# RS485_RX.net
KiCad netlist of a schematic drawn in EAGLE
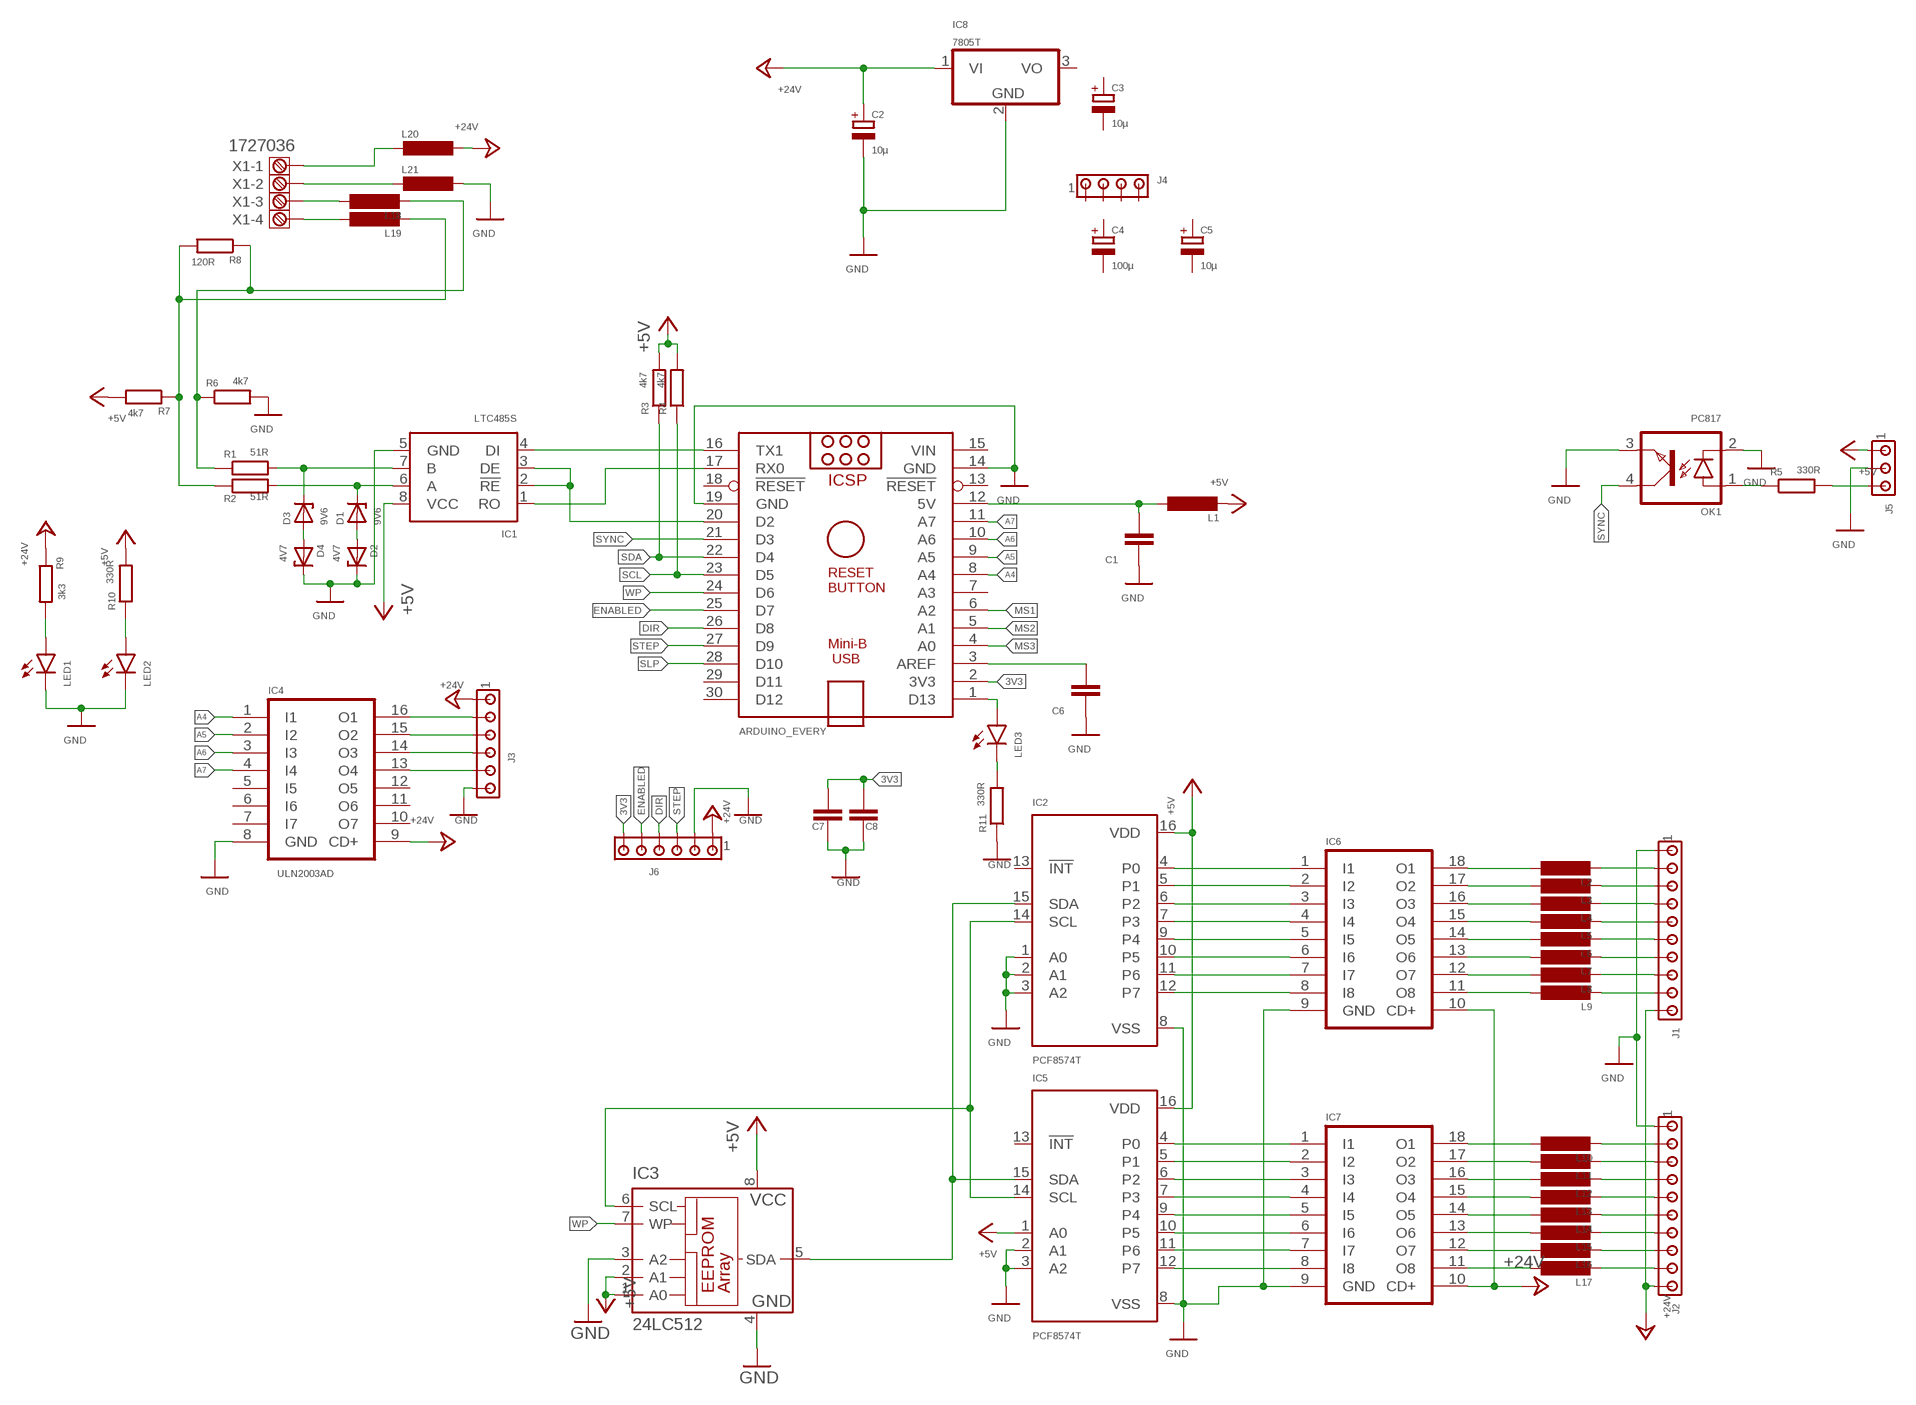
[diagram p0: schematic, sheet 1]

(export (version "E")
  (design (tool "Eeschema 10.0.6"))
  (components
    (comp (ref "ARDUINO_EVERY")
      (value "ARDUINO_NANO")
      (footprint "eagle-import:ARDUINO_NANO")
      (libsource (lib "eagle-import") (part "ARDUINO_NANO"))
    )
    (comp (ref "C1")
      (value "C-EUC0805K")
      (footprint "eagle-import:C0805K")
      (libsource (lib "eagle-import") (part "C-EUC0805K"))
    )
    (comp (ref "C2")
      (value "10µ")
      (footprint "eagle-import:150CLZ-0810")
      (libsource (lib "eagle-import") (part "CPOL-EU150CLZ-0810"))
    )
    (comp (ref "C3")
      (value "10µ")
      (footprint "eagle-import:150CLZ-0810")
      (libsource (lib "eagle-import") (part "CPOL-EU150CLZ-0810"))
    )
    (comp (ref "C4")
      (value "100µ")
      (footprint "eagle-import:150CLZ-0810")
      (libsource (lib "eagle-import") (part "CPOL-EU150CLZ-0810"))
    )
    (comp (ref "C5")
      (value "10µ")
      (footprint "eagle-import:150CLZ-0810")
      (libsource (lib "eagle-import") (part "CPOL-EU150CLZ-0810"))
    )
    (comp (ref "C6")
      (value "C-EUC0805K")
      (footprint "eagle-import:C0805K")
      (libsource (lib "eagle-import") (part "C-EUC0805K"))
    )
    (comp (ref "C7")
      (value "C-EUC0805K")
      (footprint "eagle-import:C0805K")
      (libsource (lib "eagle-import") (part "C-EUC0805K"))
    )
    (comp (ref "C8")
      (value "C-EUC0805K")
      (footprint "eagle-import:C0805K")
      (libsource (lib "eagle-import") (part "C-EUC0805K"))
    )
    (comp (ref "D1")
      (value "9V6")
      (footprint "eagle-import:SOD80C")
      (libsource (lib "eagle-import") (part "ZENER-DIODESOD80C"))
    )
    (comp (ref "D2")
      (value "4V7")
      (footprint "eagle-import:SOD80C")
      (libsource (lib "eagle-import") (part "ZENER-DIODESOD80C"))
    )
    (comp (ref "D3")
      (value "9V6")
      (footprint "eagle-import:SOD80C")
      (libsource (lib "eagle-import") (part "ZENER-DIODESOD80C"))
    )
    (comp (ref "D4")
      (value "4V7")
      (footprint "eagle-import:SOD80C")
      (libsource (lib "eagle-import") (part "ZENER-DIODESOD80C"))
    )
    (comp (ref "IC1")
      (value "LTC485S")
      (footprint "eagle-import:SOIC8")
      (libsource (lib "eagle-import") (part "LTC485S"))
    )
    (comp (ref "IC2")
      (value "PCF8574T")
      (footprint "eagle-import:SO16W")
      (fields (field (name "MPN") "PCF8574T/3,512"))
      (libsource (lib "eagle-import") (part "PCF8574T"))
    )
    (comp (ref "IC3")
      (value "24LC512")
      (footprint "eagle-import:SO-08")
      (fields (field (name "MF") "MICROCHIP") (field (name "MPN") "24LC128-I/SNG"))
      (libsource (lib "eagle-import") (part "24SNLC128"))
    )
    (comp (ref "IC4")
      (value "ULN2003AD")
      (footprint "eagle-import:SO16")
      (libsource (lib "eagle-import") (part "ULN2003AD"))
    )
    (comp (ref "IC5")
      (value "PCF8574T")
      (footprint "eagle-import:SO16W")
      (fields (field (name "MPN") "PCF8574T/3,512"))
      (libsource (lib "eagle-import") (part "PCF8574T"))
    )
    (comp (ref "IC6")
      (value "ULN2803A")
      (footprint "eagle-import:DIL18")
      (libsource (lib "eagle-import") (part "ULN2803A"))
    )
    (comp (ref "IC7")
      (value "ULN2803A")
      (footprint "eagle-import:DIL18")
      (libsource (lib "eagle-import") (part "ULN2803A"))
    )
    (comp (ref "IC8")
      (value "7805T")
      (footprint "eagle-import:TO220H")
      (libsource (lib "eagle-import") (part "78T05"))
    )
    (comp (ref "J1")
      (value "MTA10-100")
      (footprint "eagle-import:10X10MTA")
      (libsource (lib "eagle-import") (part "MTA10-100"))
    )
    (comp (ref "J2")
      (value "MTA10-100")
      (footprint "eagle-import:10X10MTA")
      (libsource (lib "eagle-import") (part "MTA10-100"))
    )
    (comp (ref "J3")
      (value "MTA06-100")
      (footprint "eagle-import:10X06MTA")
      (libsource (lib "eagle-import") (part "MTA06-100"))
    )
    (comp (ref "J4")
      (value "MTA04-156")
      (footprint "eagle-import:1X4MTA")
      (libsource (lib "eagle-import") (part "MTA04-156"))
    )
    (comp (ref "J5")
      (value "MTA03-100")
      (footprint "eagle-import:10X03MTA")
      (libsource (lib "eagle-import") (part "MTA03-100"))
    )
    (comp (ref "J6")
      (value "MTA06-100")
      (footprint "eagle-import:10X06MTA")
      (libsource (lib "eagle-import") (part "MTA06-100"))
    )
    (comp (ref "L1")
      (value "L-EUL1812")
      (footprint "eagle-import:L1812")
      (libsource (lib "eagle-import") (part "L-EUL1812"))
    )
    (comp (ref "L2")
      (value "L-EUL1812")
      (footprint "eagle-import:L1812")
      (libsource (lib "eagle-import") (part "L-EUL1812"))
    )
    (comp (ref "L3")
      (value "L-EUL1812")
      (footprint "eagle-import:L1812")
      (libsource (lib "eagle-import") (part "L-EUL1812"))
    )
    (comp (ref "L4")
      (value "L-EUL1812")
      (footprint "eagle-import:L1812")
      (libsource (lib "eagle-import") (part "L-EUL1812"))
    )
    (comp (ref "L5")
      (value "L-EUL1812")
      (footprint "eagle-import:L1812")
      (libsource (lib "eagle-import") (part "L-EUL1812"))
    )
    (comp (ref "L6")
      (value "L-EUL1812")
      (footprint "eagle-import:L1812")
      (libsource (lib "eagle-import") (part "L-EUL1812"))
    )
    (comp (ref "L7")
      (value "L-EUL1812")
      (footprint "eagle-import:L1812")
      (libsource (lib "eagle-import") (part "L-EUL1812"))
    )
    (comp (ref "L8")
      (value "L-EUL1812")
      (footprint "eagle-import:L1812")
      (libsource (lib "eagle-import") (part "L-EUL1812"))
    )
    (comp (ref "L9")
      (value "L-EUL1812")
      (footprint "eagle-import:L1812")
      (libsource (lib "eagle-import") (part "L-EUL1812"))
    )
    (comp (ref "L10")
      (value "L-EUL1812")
      (footprint "eagle-import:L1812")
      (libsource (lib "eagle-import") (part "L-EUL1812"))
    )
    (comp (ref "L11")
      (value "L-EUL1812")
      (footprint "eagle-import:L1812")
      (libsource (lib "eagle-import") (part "L-EUL1812"))
    )
    (comp (ref "L12")
      (value "L-EUL1812")
      (footprint "eagle-import:L1812")
      (libsource (lib "eagle-import") (part "L-EUL1812"))
    )
    (comp (ref "L13")
      (value "L-EUL1812")
      (footprint "eagle-import:L1812")
      (libsource (lib "eagle-import") (part "L-EUL1812"))
    )
    (comp (ref "L14")
      (value "L-EUL1812")
      (footprint "eagle-import:L1812")
      (libsource (lib "eagle-import") (part "L-EUL1812"))
    )
    (comp (ref "L15")
      (value "L-EUL1812")
      (footprint "eagle-import:L1812")
      (libsource (lib "eagle-import") (part "L-EUL1812"))
    )
    (comp (ref "L16")
      (value "L-EUL1812")
      (footprint "eagle-import:L1812")
      (libsource (lib "eagle-import") (part "L-EUL1812"))
    )
    (comp (ref "L17")
      (value "L-EUL1812")
      (footprint "eagle-import:L1812")
      (libsource (lib "eagle-import") (part "L-EUL1812"))
    )
    (comp (ref "L18")
      (value "L-EUL1812")
      (footprint "eagle-import:L1812")
      (libsource (lib "eagle-import") (part "L-EUL1812"))
    )
    (comp (ref "L19")
      (value "L-EUL1812")
      (footprint "eagle-import:L1812")
      (libsource (lib "eagle-import") (part "L-EUL1812"))
    )
    (comp (ref "L20")
      (value "DO3316P")
      (footprint "eagle-import:DO3316P")
      (libsource (lib "eagle-import") (part "DO3316P"))
    )
    (comp (ref "L21")
      (value "DO3316P")
      (footprint "eagle-import:DO3316P")
      (libsource (lib "eagle-import") (part "DO3316P"))
    )
    (comp (ref "LED1")
      (value "LEDCHIPLED_1206")
      (footprint "eagle-import:CHIPLED_1206")
      (libsource (lib "eagle-import") (part "LEDCHIPLED_1206"))
    )
    (comp (ref "LED2")
      (value "LEDCHIPLED_1206")
      (footprint "eagle-import:CHIPLED_1206")
      (libsource (lib "eagle-import") (part "LEDCHIPLED_1206"))
    )
    (comp (ref "LED3")
      (value "LEDCHIPLED_1206")
      (footprint "eagle-import:CHIPLED_1206")
      (libsource (lib "eagle-import") (part "LEDCHIPLED_1206"))
    )
    (comp (ref "OK1")
      (value "PC817")
      (footprint "eagle-import:DIL04")
      (fields (field (name "MPN") "PC817X4J000F"))
      (libsource (lib "eagle-import") (part "PC817"))
    )
    (comp (ref "R1")
      (value "51R")
      (footprint "eagle-import:R0805")
      (libsource (lib "eagle-import") (part "R-EU_R0805"))
    )
    (comp (ref "R2")
      (value "51R")
      (footprint "eagle-import:R0805")
      (libsource (lib "eagle-import") (part "R-EU_R0805"))
    )
    (comp (ref "R3")
      (value "4k7")
      (footprint "eagle-import:R0805")
      (libsource (lib "eagle-import") (part "R-EU_R0805"))
    )
    (comp (ref "R4")
      (value "4k7")
      (footprint "eagle-import:R0805")
      (libsource (lib "eagle-import") (part "R-EU_R0805"))
    )
    (comp (ref "R5")
      (value "330R")
      (footprint "eagle-import:R0805")
      (libsource (lib "eagle-import") (part "R-EU_R0805"))
    )
    (comp (ref "R6")
      (value "4k7")
      (footprint "eagle-import:R0805")
      (libsource (lib "eagle-import") (part "R-EU_R0805"))
    )
    (comp (ref "R7")
      (value "4k7")
      (footprint "eagle-import:R0805")
      (libsource (lib "eagle-import") (part "R-EU_R0805"))
    )
    (comp (ref "R8")
      (value "120R")
      (footprint "eagle-import:R0805")
      (libsource (lib "eagle-import") (part "R-EU_R0805"))
    )
    (comp (ref "R9")
      (value "3k3")
      (footprint "eagle-import:R0805")
      (libsource (lib "eagle-import") (part "R-EU_R0805"))
    )
    (comp (ref "R10")
      (value "330R")
      (footprint "eagle-import:R0805")
      (libsource (lib "eagle-import") (part "R-EU_R0805"))
    )
    (comp (ref "R11")
      (value "330R")
      (footprint "eagle-import:R0805")
      (libsource (lib "eagle-import") (part "R-EU_R0805"))
    )
    (comp (ref "X1")
      (value "1727036")
      (footprint "eagle-import:1727036")
      (fields (field (name "MF") "FARNELL"))
      (libsource (lib "eagle-import") (part "1727036"))
    )
  )
  (nets
    (net (code "1") (name "+5V") (class "Default")
      (node (ref "IC1") (pin "8") (pinfunction "VCC_8") (pintype "input"))
      (node (ref "IC2") (pin "16") (pinfunction "VDD_16") (pintype "power_in"))
      (node (ref "IC3") (pin "1") (pinfunction "A0_1") (pintype "input"))
      (node (ref "IC3") (pin "2") (pinfunction "A1_2") (pintype "input"))
      (node (ref "IC3") (pin "8") (pinfunction "VCC_8") (pintype "power_in"))
      (node (ref "IC5") (pin "1") (pinfunction "A0_1") (pintype "input"))
      (node (ref "IC5") (pin "16") (pinfunction "VDD_16") (pintype "power_in"))
      (node (ref "J5") (pin "1") (pinfunction "1_1") (pintype "passive"))
      (node (ref "L1") (pin "2") (pinfunction "2_2") (pintype "passive"))
      (node (ref "R10") (pin "2") (pinfunction "2_2") (pintype "passive"))
      (node (ref "R3") (pin "2") (pinfunction "2_2") (pintype "passive"))
      (node (ref "R4") (pin "2") (pinfunction "2_2") (pintype "passive"))
      (node (ref "R7") (pin "2") (pinfunction "2_2") (pintype "passive"))
    )
    (net (code "2") (name "+24V") (class "Default")
      (node (ref "C2") (pin "+") (pinfunction "+_+") (pintype "passive"))
      (node (ref "IC4") (pin "9") (pinfunction "CD+_9") (pintype "passive"))
      (node (ref "IC6") (pin "10") (pinfunction "CD+_10") (pintype "passive"))
      (node (ref "IC7") (pin "10") (pinfunction "CD+_10") (pintype "passive"))
      (node (ref "IC8") (pin "1") (pinfunction "VI_1") (pintype "input"))
      (node (ref "J1") (pin "10") (pinfunction "10_10") (pintype "passive"))
      (node (ref "J2") (pin "10") (pinfunction "10_10") (pintype "passive"))
      (node (ref "J3") (pin "1") (pinfunction "1_1") (pintype "passive"))
      (node (ref "J6") (pin "1") (pinfunction "1_1") (pintype "passive"))
      (node (ref "L20") (pin "2") (pinfunction "2_2") (pintype "passive"))
      (node (ref "R9") (pin "1") (pinfunction "1_1") (pintype "passive"))
    )
    (net (code "3") (name "/VIN") (class "Default")
      (node (ref "ARDUINO_EVERY") (pin "15") (pinfunction "VIN_15") (pintype "power_in"))
    )
    (net (code "4") (name "3V3") (class "Default")
      (node (ref "ARDUINO_EVERY") (pin "2") (pinfunction "3V3_2") (pintype "output"))
      (node (ref "C7") (pin "1") (pinfunction "1_1") (pintype "passive"))
      (node (ref "C8") (pin "1") (pinfunction "1_1") (pintype "passive"))
      (node (ref "J6") (pin "6") (pinfunction "6_6") (pintype "passive"))
    )
    (net (code "5") (name "A4") (class "Default")
      (node (ref "ARDUINO_EVERY") (pin "8") (pinfunction "A4_8") (pintype "bidirectional"))
      (node (ref "IC4") (pin "1") (pinfunction "I1_1") (pintype "input"))
    )
    (net (code "6") (name "A5") (class "Default")
      (node (ref "ARDUINO_EVERY") (pin "9") (pinfunction "A5_9") (pintype "bidirectional"))
      (node (ref "IC4") (pin "2") (pinfunction "I2_2") (pintype "input"))
    )
    (net (code "7") (name "A6") (class "Default")
      (node (ref "ARDUINO_EVERY") (pin "10") (pinfunction "A6_10") (pintype "bidirectional"))
      (node (ref "IC4") (pin "3") (pinfunction "I3_3") (pintype "input"))
    )
    (net (code "8") (name "A7") (class "Default")
      (node (ref "ARDUINO_EVERY") (pin "11") (pinfunction "A7_11") (pintype "bidirectional"))
      (node (ref "IC4") (pin "4") (pinfunction "I4_4") (pintype "input"))
    )
    (net (code "9") (name "DIR") (class "Default")
      (node (ref "ARDUINO_EVERY") (pin "26") (pinfunction "D8_26") (pintype "bidirectional"))
      (node (ref "J6") (pin "4") (pinfunction "4_4") (pintype "passive"))
    )
    (net (code "10") (name "ENABLED") (class "Default")
      (node (ref "ARDUINO_EVERY") (pin "25") (pinfunction "D7_25") (pintype "bidirectional"))
      (node (ref "J6") (pin "5") (pinfunction "5_5") (pintype "passive"))
    )
    (net (code "11") (name "GND") (class "Default")
      (node (ref "ARDUINO_EVERY") (pin "14") (pinfunction "GND_14") (pintype "power_in"))
      (node (ref "ARDUINO_EVERY") (pin "19") (pinfunction "GND_19") (pintype "power_in"))
      (node (ref "C1") (pin "2") (pinfunction "2_2") (pintype "passive"))
      (node (ref "C2") (pin "-") (pinfunction "-_-") (pintype "passive"))
      (node (ref "C6") (pin "2") (pinfunction "2_2") (pintype "passive"))
      (node (ref "C7") (pin "2") (pinfunction "2_2") (pintype "passive"))
      (node (ref "C8") (pin "2") (pinfunction "2_2") (pintype "passive"))
      (node (ref "D2") (pin "C") (pinfunction "C_C") (pintype "passive"))
      (node (ref "D4") (pin "C") (pinfunction "C_C") (pintype "passive"))
      (node (ref "IC1") (pin "5") (pinfunction "GND_5") (pintype "input"))
      (node (ref "IC2") (pin "1") (pinfunction "A0_1") (pintype "input"))
      (node (ref "IC2") (pin "2") (pinfunction "A1_2") (pintype "input"))
      (node (ref "IC2") (pin "3") (pinfunction "A2_3") (pintype "input"))
      (node (ref "IC2") (pin "8") (pinfunction "VSS_8") (pintype "power_in"))
      (node (ref "IC3") (pin "3") (pinfunction "A2_3") (pintype "input"))
      (node (ref "IC3") (pin "4") (pinfunction "GND_4") (pintype "power_in"))
      (node (ref "IC4") (pin "8") (pinfunction "GND_8") (pintype "power_in"))
      (node (ref "IC5") (pin "2") (pinfunction "A1_2") (pintype "input"))
      (node (ref "IC5") (pin "3") (pinfunction "A2_3") (pintype "input"))
      (node (ref "IC5") (pin "8") (pinfunction "VSS_8") (pintype "power_in"))
      (node (ref "IC6") (pin "9") (pinfunction "GND_9") (pintype "power_in"))
      (node (ref "IC7") (pin "9") (pinfunction "GND_9") (pintype "power_in"))
      (node (ref "IC8") (pin "2") (pinfunction "GND_2") (pintype "passive"))
      (node (ref "J1") (pin "1") (pinfunction "1_1") (pintype "passive"))
      (node (ref "J2") (pin "1") (pinfunction "1_1") (pintype "passive"))
      (node (ref "J3") (pin "6") (pinfunction "6_6") (pintype "passive"))
      (node (ref "J5") (pin "2") (pinfunction "2_2") (pintype "passive"))
      (node (ref "J6") (pin "2") (pinfunction "2_2") (pintype "passive"))
      (node (ref "L21") (pin "2") (pinfunction "2_2") (pintype "passive"))
      (node (ref "LED1") (pin "C") (pinfunction "C_C") (pintype "passive"))
      (node (ref "LED2") (pin "C") (pinfunction "C_C") (pintype "passive"))
      (node (ref "OK1") (pin "2") (pinfunction "C_2") (pintype "passive"))
      (node (ref "OK1") (pin "3") (pinfunction "EMIT_3") (pintype "passive"))
      (node (ref "R11") (pin "1") (pinfunction "1_1") (pintype "passive"))
      (node (ref "R6") (pin "2") (pinfunction "2_2") (pintype "passive"))
    )
    (net (code "12") (name "MS1") (class "Default")
      (node (ref "ARDUINO_EVERY") (pin "6") (pinfunction "A2_6") (pintype "bidirectional"))
    )
    (net (code "13") (name "MS2") (class "Default")
      (node (ref "ARDUINO_EVERY") (pin "5") (pinfunction "A1_5") (pintype "bidirectional"))
    )
    (net (code "14") (name "MS3") (class "Default")
      (node (ref "ARDUINO_EVERY") (pin "4") (pinfunction "A0_4") (pintype "bidirectional"))
    )
    (net (code "15") (name "Net-(ARDUINO_EVERY-5V)") (class "Default")
      (node (ref "ARDUINO_EVERY") (pin "12") (pinfunction "5V_12") (pintype "power_in"))
      (node (ref "C1") (pin "1") (pinfunction "1_1") (pintype "passive"))
      (node (ref "L1") (pin "1") (pinfunction "1_1") (pintype "passive"))
    )
    (net (code "16") (name "Net-(ARDUINO_EVERY-AREF)") (class "Default")
      (node (ref "ARDUINO_EVERY") (pin "3") (pinfunction "AREF_3") (pintype "input"))
      (node (ref "C6") (pin "1") (pinfunction "1_1") (pintype "passive"))
    )
    (net (code "17") (name "Net-(ARDUINO_EVERY-D2)") (class "Default")
      (node (ref "ARDUINO_EVERY") (pin "20") (pinfunction "D2_20") (pintype "bidirectional"))
      (node (ref "IC1") (pin "2") (pinfunction "~{RE}_2") (pintype "input"))
      (node (ref "IC1") (pin "3") (pinfunction "DE_3") (pintype "input"))
    )
    (net (code "18") (name "Net-(ARDUINO_EVERY-D13)") (class "Default")
      (node (ref "ARDUINO_EVERY") (pin "1") (pinfunction "D13_1") (pintype "bidirectional"))
      (node (ref "LED3") (pin "A") (pinfunction "A_A") (pintype "passive"))
    )
    (net (code "19") (name "Net-(ARDUINO_EVERY-RX0)") (class "Default")
      (node (ref "ARDUINO_EVERY") (pin "17") (pinfunction "RX0_17") (pintype "bidirectional"))
      (node (ref "IC1") (pin "1") (pinfunction "RO_1") (pintype "output"))
    )
    (net (code "20") (name "Net-(ARDUINO_EVERY-TX1)") (class "Default")
      (node (ref "ARDUINO_EVERY") (pin "16") (pinfunction "TX1_16") (pintype "bidirectional"))
      (node (ref "IC1") (pin "4") (pinfunction "DI_4") (pintype "input"))
    )
    (net (code "21") (name "Net-(D1-PadA)") (class "Default")
      (node (ref "D1") (pin "A") (pinfunction "A_A") (pintype "passive"))
      (node (ref "D2") (pin "A") (pinfunction "A_A") (pintype "passive"))
    )
    (net (code "22") (name "Net-(D3-PadA)") (class "Default")
      (node (ref "D3") (pin "A") (pinfunction "A_A") (pintype "passive"))
      (node (ref "D4") (pin "A") (pinfunction "A_A") (pintype "passive"))
    )
    (net (code "23") (name "Net-(IC1-A)") (class "Default")
      (node (ref "D1") (pin "C") (pinfunction "C_C") (pintype "passive"))
      (node (ref "IC1") (pin "6") (pinfunction "A_6") (pintype "bidirectional"))
      (node (ref "R2") (pin "2") (pinfunction "2_2") (pintype "passive"))
    )
    (net (code "24") (name "Net-(IC1-B)") (class "Default")
      (node (ref "D3") (pin "C") (pinfunction "C_C") (pintype "passive"))
      (node (ref "IC1") (pin "7") (pinfunction "B_7") (pintype "bidirectional"))
      (node (ref "R1") (pin "2") (pinfunction "2_2") (pintype "passive"))
    )
    (net (code "25") (name "Net-(IC2-P0)") (class "Default")
      (node (ref "IC2") (pin "4") (pinfunction "P0_4") (pintype "bidirectional"))
      (node (ref "IC6") (pin "1") (pinfunction "I1_1") (pintype "input"))
    )
    (net (code "26") (name "Net-(IC2-P1)") (class "Default")
      (node (ref "IC2") (pin "5") (pinfunction "P1_5") (pintype "bidirectional"))
      (node (ref "IC6") (pin "2") (pinfunction "I2_2") (pintype "input"))
    )
    (net (code "27") (name "Net-(IC2-P2)") (class "Default")
      (node (ref "IC2") (pin "6") (pinfunction "P2_6") (pintype "bidirectional"))
      (node (ref "IC6") (pin "3") (pinfunction "I3_3") (pintype "input"))
    )
    (net (code "28") (name "Net-(IC2-P3)") (class "Default")
      (node (ref "IC2") (pin "7") (pinfunction "P3_7") (pintype "bidirectional"))
      (node (ref "IC6") (pin "4") (pinfunction "I4_4") (pintype "input"))
    )
    (net (code "29") (name "Net-(IC2-P4)") (class "Default")
      (node (ref "IC2") (pin "9") (pinfunction "P4_9") (pintype "bidirectional"))
      (node (ref "IC6") (pin "5") (pinfunction "I5_5") (pintype "input"))
    )
    (net (code "30") (name "Net-(IC2-P5)") (class "Default")
      (node (ref "IC2") (pin "10") (pinfunction "P5_10") (pintype "bidirectional"))
      (node (ref "IC6") (pin "6") (pinfunction "I6_6") (pintype "input"))
    )
    (net (code "31") (name "Net-(IC2-P6)") (class "Default")
      (node (ref "IC2") (pin "11") (pinfunction "P6_11") (pintype "bidirectional"))
      (node (ref "IC6") (pin "7") (pinfunction "I7_7") (pintype "input"))
    )
    (net (code "32") (name "Net-(IC2-P7)") (class "Default")
      (node (ref "IC2") (pin "12") (pinfunction "P7_12") (pintype "bidirectional"))
      (node (ref "IC6") (pin "8") (pinfunction "I8_8") (pintype "input"))
    )
    (net (code "33") (name "Net-(IC4-O1)") (class "Default")
      (node (ref "IC4") (pin "16") (pinfunction "O1_16") (pintype "open_collector"))
      (node (ref "J3") (pin "2") (pinfunction "2_2") (pintype "passive"))
    )
    (net (code "34") (name "Net-(IC4-O2)") (class "Default")
      (node (ref "IC4") (pin "15") (pinfunction "O2_15") (pintype "open_collector"))
      (node (ref "J3") (pin "3") (pinfunction "3_3") (pintype "passive"))
    )
    (net (code "35") (name "Net-(IC4-O3)") (class "Default")
      (node (ref "IC4") (pin "14") (pinfunction "O3_14") (pintype "open_collector"))
      (node (ref "J3") (pin "4") (pinfunction "4_4") (pintype "passive"))
    )
    (net (code "36") (name "Net-(IC4-O4)") (class "Default")
      (node (ref "IC4") (pin "13") (pinfunction "O4_13") (pintype "open_collector"))
      (node (ref "J3") (pin "5") (pinfunction "5_5") (pintype "passive"))
    )
    (net (code "37") (name "Net-(IC5-P0)") (class "Default")
      (node (ref "IC5") (pin "4") (pinfunction "P0_4") (pintype "bidirectional"))
      (node (ref "IC7") (pin "1") (pinfunction "I1_1") (pintype "input"))
    )
    (net (code "38") (name "Net-(IC5-P1)") (class "Default")
      (node (ref "IC5") (pin "5") (pinfunction "P1_5") (pintype "bidirectional"))
      (node (ref "IC7") (pin "2") (pinfunction "I2_2") (pintype "input"))
    )
    (net (code "39") (name "Net-(IC5-P2)") (class "Default")
      (node (ref "IC5") (pin "6") (pinfunction "P2_6") (pintype "bidirectional"))
      (node (ref "IC7") (pin "3") (pinfunction "I3_3") (pintype "input"))
    )
    (net (code "40") (name "Net-(IC5-P3)") (class "Default")
      (node (ref "IC5") (pin "7") (pinfunction "P3_7") (pintype "bidirectional"))
      (node (ref "IC7") (pin "4") (pinfunction "I4_4") (pintype "input"))
    )
    (net (code "41") (name "Net-(IC5-P4)") (class "Default")
      (node (ref "IC5") (pin "9") (pinfunction "P4_9") (pintype "bidirectional"))
      (node (ref "IC7") (pin "5") (pinfunction "I5_5") (pintype "input"))
    )
    (net (code "42") (name "Net-(IC5-P5)") (class "Default")
      (node (ref "IC5") (pin "10") (pinfunction "P5_10") (pintype "bidirectional"))
      (node (ref "IC7") (pin "6") (pinfunction "I6_6") (pintype "input"))
    )
    (net (code "43") (name "Net-(IC5-P6)") (class "Default")
      (node (ref "IC5") (pin "11") (pinfunction "P6_11") (pintype "bidirectional"))
      (node (ref "IC7") (pin "7") (pinfunction "I7_7") (pintype "input"))
    )
    (net (code "44") (name "Net-(IC5-P7)") (class "Default")
      (node (ref "IC5") (pin "12") (pinfunction "P7_12") (pintype "bidirectional"))
      (node (ref "IC7") (pin "8") (pinfunction "I8_8") (pintype "input"))
    )
    (net (code "45") (name "Net-(IC6-O1)") (class "Default")
      (node (ref "IC6") (pin "18") (pinfunction "O1_18") (pintype "open_collector"))
      (node (ref "L2") (pin "1") (pinfunction "1_1") (pintype "passive"))
    )
    (net (code "46") (name "Net-(IC6-O2)") (class "Default")
      (node (ref "IC6") (pin "17") (pinfunction "O2_17") (pintype "open_collector"))
      (node (ref "L3") (pin "1") (pinfunction "1_1") (pintype "passive"))
    )
    (net (code "47") (name "Net-(IC6-O3)") (class "Default")
      (node (ref "IC6") (pin "16") (pinfunction "O3_16") (pintype "open_collector"))
      (node (ref "L4") (pin "1") (pinfunction "1_1") (pintype "passive"))
    )
    (net (code "48") (name "Net-(IC6-O4)") (class "Default")
      (node (ref "IC6") (pin "15") (pinfunction "O4_15") (pintype "open_collector"))
      (node (ref "L5") (pin "1") (pinfunction "1_1") (pintype "passive"))
    )
    (net (code "49") (name "Net-(IC6-O5)") (class "Default")
      (node (ref "IC6") (pin "14") (pinfunction "O5_14") (pintype "open_collector"))
      (node (ref "L6") (pin "1") (pinfunction "1_1") (pintype "passive"))
    )
    (net (code "50") (name "Net-(IC6-O6)") (class "Default")
      (node (ref "IC6") (pin "13") (pinfunction "O6_13") (pintype "open_collector"))
      (node (ref "L7") (pin "1") (pinfunction "1_1") (pintype "passive"))
    )
    (net (code "51") (name "Net-(IC6-O7)") (class "Default")
      (node (ref "IC6") (pin "12") (pinfunction "O7_12") (pintype "open_collector"))
      (node (ref "L8") (pin "1") (pinfunction "1_1") (pintype "passive"))
    )
    (net (code "52") (name "Net-(IC6-O8)") (class "Default")
      (node (ref "IC6") (pin "11") (pinfunction "O8_11") (pintype "open_collector"))
      (node (ref "L9") (pin "1") (pinfunction "1_1") (pintype "passive"))
    )
    (net (code "53") (name "Net-(IC7-O1)") (class "Default")
      (node (ref "IC7") (pin "18") (pinfunction "O1_18") (pintype "open_collector"))
      (node (ref "L10") (pin "1") (pinfunction "1_1") (pintype "passive"))
    )
    (net (code "54") (name "Net-(IC7-O2)") (class "Default")
      (node (ref "IC7") (pin "17") (pinfunction "O2_17") (pintype "open_collector"))
      (node (ref "L11") (pin "1") (pinfunction "1_1") (pintype "passive"))
    )
    (net (code "55") (name "Net-(IC7-O3)") (class "Default")
      (node (ref "IC7") (pin "16") (pinfunction "O3_16") (pintype "open_collector"))
      (node (ref "L12") (pin "1") (pinfunction "1_1") (pintype "passive"))
    )
    (net (code "56") (name "Net-(IC7-O4)") (class "Default")
      (node (ref "IC7") (pin "15") (pinfunction "O4_15") (pintype "open_collector"))
      (node (ref "L13") (pin "1") (pinfunction "1_1") (pintype "passive"))
    )
    (net (code "57") (name "Net-(IC7-O5)") (class "Default")
      (node (ref "IC7") (pin "14") (pinfunction "O5_14") (pintype "open_collector"))
      (node (ref "L14") (pin "1") (pinfunction "1_1") (pintype "passive"))
    )
    (net (code "58") (name "Net-(IC7-O6)") (class "Default")
      (node (ref "IC7") (pin "13") (pinfunction "O6_13") (pintype "open_collector"))
      (node (ref "L15") (pin "1") (pinfunction "1_1") (pintype "passive"))
    )
    (net (code "59") (name "Net-(IC7-O7)") (class "Default")
      (node (ref "IC7") (pin "12") (pinfunction "O7_12") (pintype "open_collector"))
      (node (ref "L16") (pin "1") (pinfunction "1_1") (pintype "passive"))
    )
    (net (code "60") (name "Net-(IC7-O8)") (class "Default")
      (node (ref "IC7") (pin "11") (pinfunction "O8_11") (pintype "open_collector"))
      (node (ref "L17") (pin "1") (pinfunction "1_1") (pintype "passive"))
    )
    (net (code "61") (name "Net-(J1-Pad2)") (class "Default")
      (node (ref "J1") (pin "2") (pinfunction "2_2") (pintype "passive"))
      (node (ref "L2") (pin "2") (pinfunction "2_2") (pintype "passive"))
    )
    (net (code "62") (name "Net-(J1-Pad3)") (class "Default")
      (node (ref "J1") (pin "3") (pinfunction "3_3") (pintype "passive"))
      (node (ref "L3") (pin "2") (pinfunction "2_2") (pintype "passive"))
    )
    (net (code "63") (name "Net-(J1-Pad4)") (class "Default")
      (node (ref "J1") (pin "4") (pinfunction "4_4") (pintype "passive"))
      (node (ref "L4") (pin "2") (pinfunction "2_2") (pintype "passive"))
    )
    (net (code "64") (name "Net-(J1-Pad5)") (class "Default")
      (node (ref "J1") (pin "5") (pinfunction "5_5") (pintype "passive"))
      (node (ref "L5") (pin "2") (pinfunction "2_2") (pintype "passive"))
    )
    (net (code "65") (name "Net-(J1-Pad6)") (class "Default")
      (node (ref "J1") (pin "6") (pinfunction "6_6") (pintype "passive"))
      (node (ref "L6") (pin "2") (pinfunction "2_2") (pintype "passive"))
    )
    (net (code "66") (name "Net-(J1-Pad7)") (class "Default")
      (node (ref "J1") (pin "7") (pinfunction "7_7") (pintype "passive"))
      (node (ref "L7") (pin "2") (pinfunction "2_2") (pintype "passive"))
    )
    (net (code "67") (name "Net-(J1-Pad8)") (class "Default")
      (node (ref "J1") (pin "8") (pinfunction "8_8") (pintype "passive"))
      (node (ref "L8") (pin "2") (pinfunction "2_2") (pintype "passive"))
    )
    (net (code "68") (name "Net-(J1-Pad9)") (class "Default")
      (node (ref "J1") (pin "9") (pinfunction "9_9") (pintype "passive"))
      (node (ref "L9") (pin "2") (pinfunction "2_2") (pintype "passive"))
    )
    (net (code "69") (name "Net-(J2-Pad2)") (class "Default")
      (node (ref "J2") (pin "2") (pinfunction "2_2") (pintype "passive"))
      (node (ref "L10") (pin "2") (pinfunction "2_2") (pintype "passive"))
    )
    (net (code "70") (name "Net-(J2-Pad3)") (class "Default")
      (node (ref "J2") (pin "3") (pinfunction "3_3") (pintype "passive"))
      (node (ref "L11") (pin "2") (pinfunction "2_2") (pintype "passive"))
    )
    (net (code "71") (name "Net-(J2-Pad4)") (class "Default")
      (node (ref "J2") (pin "4") (pinfunction "4_4") (pintype "passive"))
      (node (ref "L12") (pin "2") (pinfunction "2_2") (pintype "passive"))
    )
    (net (code "72") (name "Net-(J2-Pad5)") (class "Default")
      (node (ref "J2") (pin "5") (pinfunction "5_5") (pintype "passive"))
      (node (ref "L13") (pin "2") (pinfunction "2_2") (pintype "passive"))
    )
    (net (code "73") (name "Net-(J2-Pad6)") (class "Default")
      (node (ref "J2") (pin "6") (pinfunction "6_6") (pintype "passive"))
      (node (ref "L14") (pin "2") (pinfunction "2_2") (pintype "passive"))
    )
    (net (code "74") (name "Net-(J2-Pad7)") (class "Default")
      (node (ref "J2") (pin "7") (pinfunction "7_7") (pintype "passive"))
      (node (ref "L15") (pin "2") (pinfunction "2_2") (pintype "passive"))
    )
    (net (code "75") (name "Net-(J2-Pad8)") (class "Default")
      (node (ref "J2") (pin "8") (pinfunction "8_8") (pintype "passive"))
      (node (ref "L16") (pin "2") (pinfunction "2_2") (pintype "passive"))
    )
    (net (code "76") (name "Net-(J2-Pad9)") (class "Default")
      (node (ref "J2") (pin "9") (pinfunction "9_9") (pintype "passive"))
      (node (ref "L17") (pin "2") (pinfunction "2_2") (pintype "passive"))
    )
    (net (code "77") (name "Net-(J5-Pad3)") (class "Default")
      (node (ref "J5") (pin "3") (pinfunction "3_3") (pintype "passive"))
      (node (ref "R5") (pin "2") (pinfunction "2_2") (pintype "passive"))
    )
    (net (code "78") (name "Net-(L18-Pad2)") (class "Default")
      (node (ref "L18") (pin "2") (pinfunction "2_2") (pintype "passive"))
      (node (ref "R1") (pin "1") (pinfunction "1_1") (pintype "passive"))
      (node (ref "R6") (pin "1") (pinfunction "1_1") (pintype "passive"))
      (node (ref "R8") (pin "1") (pinfunction "1_1") (pintype "passive"))
    )
    (net (code "79") (name "Net-(L19-Pad2)") (class "Default")
      (node (ref "L19") (pin "2") (pinfunction "2_2") (pintype "passive"))
      (node (ref "R2") (pin "1") (pinfunction "1_1") (pintype "passive"))
      (node (ref "R7") (pin "1") (pinfunction "1_1") (pintype "passive"))
      (node (ref "R8") (pin "2") (pinfunction "2_2") (pintype "passive"))
    )
    (net (code "80") (name "Net-(L20-Pad1)") (class "Default")
      (node (ref "L20") (pin "1") (pinfunction "1_1") (pintype "passive"))
      (node (ref "X1") (pin "1") (pinfunction "1_1") (pintype "passive"))
    )
    (net (code "81") (name "Net-(LED1-PadA)") (class "Default")
      (node (ref "LED1") (pin "A") (pinfunction "A_A") (pintype "passive"))
      (node (ref "R9") (pin "2") (pinfunction "2_2") (pintype "passive"))
    )
    (net (code "82") (name "Net-(LED2-PadA)") (class "Default")
      (node (ref "LED2") (pin "A") (pinfunction "A_A") (pintype "passive"))
      (node (ref "R10") (pin "1") (pinfunction "1_1") (pintype "passive"))
    )
    (net (code "83") (name "Net-(LED3-PadC)") (class "Default")
      (node (ref "LED3") (pin "C") (pinfunction "C_C") (pintype "passive"))
      (node (ref "R11") (pin "2") (pinfunction "2_2") (pintype "passive"))
    )
    (net (code "84") (name "Net-(OK1-A)") (class "Default")
      (node (ref "OK1") (pin "1") (pinfunction "A_1") (pintype "passive"))
      (node (ref "R5") (pin "1") (pinfunction "1_1") (pintype "passive"))
    )
    (net (code "85") (name "Net-(X1B-1)") (class "Default")
      (node (ref "L21") (pin "1") (pinfunction "1_1") (pintype "passive"))
      (node (ref "X1") (pin "2") (pinfunction "1_2") (pintype "passive"))
    )
    (net (code "86") (name "Net-(X1C-1)") (class "Default")
      (node (ref "L18") (pin "1") (pinfunction "1_1") (pintype "passive"))
      (node (ref "X1") (pin "3") (pinfunction "1_3") (pintype "passive"))
    )
    (net (code "87") (name "Net-(X1D-1)") (class "Default")
      (node (ref "L19") (pin "1") (pinfunction "1_1") (pintype "passive"))
      (node (ref "X1") (pin "4") (pinfunction "1_4") (pintype "passive"))
    )
    (net (code "88") (name "SCL") (class "Default")
      (node (ref "ARDUINO_EVERY") (pin "23") (pinfunction "D5_23") (pintype "bidirectional"))
      (node (ref "IC2") (pin "14") (pinfunction "SCL_14") (pintype "input"))
      (node (ref "IC3") (pin "6") (pinfunction "SCL_6") (pintype "input"))
      (node (ref "IC5") (pin "14") (pinfunction "SCL_14") (pintype "input"))
      (node (ref "R4") (pin "1") (pinfunction "1_1") (pintype "passive"))
    )
    (net (code "89") (name "SDA") (class "Default")
      (node (ref "ARDUINO_EVERY") (pin "22") (pinfunction "D4_22") (pintype "bidirectional"))
      (node (ref "IC2") (pin "15") (pinfunction "SDA_15") (pintype "bidirectional"))
      (node (ref "IC3") (pin "5") (pinfunction "SDA_5") (pintype "bidirectional"))
      (node (ref "IC5") (pin "15") (pinfunction "SDA_15") (pintype "bidirectional"))
      (node (ref "R3") (pin "1") (pinfunction "1_1") (pintype "passive"))
    )
    (net (code "90") (name "SLP") (class "Default")
      (node (ref "ARDUINO_EVERY") (pin "28") (pinfunction "D10_28") (pintype "bidirectional"))
    )
    (net (code "91") (name "STEP") (class "Default")
      (node (ref "ARDUINO_EVERY") (pin "27") (pinfunction "D9_27") (pintype "bidirectional"))
      (node (ref "J6") (pin "3") (pinfunction "3_3") (pintype "passive"))
    )
    (net (code "92") (name "SYNC") (class "Default")
      (node (ref "ARDUINO_EVERY") (pin "21") (pinfunction "D3_21") (pintype "bidirectional"))
      (node (ref "OK1") (pin "4") (pinfunction "COL_4") (pintype "passive"))
    )
    (net (code "93") (name "WP") (class "Default")
      (node (ref "ARDUINO_EVERY") (pin "24") (pinfunction "D6_24") (pintype "bidirectional"))
      (node (ref "IC3") (pin "7") (pinfunction "WP_7") (pintype "input"))
    )
    (net (code "94") (name "unconnected-(ARDUINO_EVERY-A3-Pad7)") (class "Default")
      (node (ref "ARDUINO_EVERY") (pin "7") (pinfunction "A3_7") (pintype "bidirectional"))
    )
    (net (code "95") (name "unconnected-(ARDUINO_EVERY-D11-Pad29)") (class "Default")
      (node (ref "ARDUINO_EVERY") (pin "29") (pinfunction "D11_29") (pintype "bidirectional"))
    )
    (net (code "96") (name "unconnected-(ARDUINO_EVERY-D12-Pad30)") (class "Default")
      (node (ref "ARDUINO_EVERY") (pin "30") (pinfunction "D12_30") (pintype "bidirectional"))
    )
    (net (code "97") (name "unconnected-(ARDUINO_EVERY-~{RESET}-Pad13)") (class "Default")
      (node (ref "ARDUINO_EVERY") (pin "13") (pinfunction "~{RESET}_13") (pintype "input"))
    )
    (net (code "98") (name "unconnected-(ARDUINO_EVERY-~{RESET}-Pad18)") (class "Default")
      (node (ref "ARDUINO_EVERY") (pin "18") (pinfunction "~{RESET}_18") (pintype "input"))
    )
    (net (code "99") (name "unconnected-(C3-Pad+)") (class "Default")
      (node (ref "C3") (pin "+") (pinfunction "+_+") (pintype "passive"))
    )
    (net (code "100") (name "unconnected-(C3-Pad-)") (class "Default")
      (node (ref "C3") (pin "-") (pinfunction "-_-") (pintype "passive"))
    )
    (net (code "101") (name "unconnected-(C4-Pad+)") (class "Default")
      (node (ref "C4") (pin "+") (pinfunction "+_+") (pintype "passive"))
    )
    (net (code "102") (name "unconnected-(C4-Pad-)") (class "Default")
      (node (ref "C4") (pin "-") (pinfunction "-_-") (pintype "passive"))
    )
    (net (code "103") (name "unconnected-(C5-Pad+)") (class "Default")
      (node (ref "C5") (pin "+") (pinfunction "+_+") (pintype "passive"))
    )
    (net (code "104") (name "unconnected-(C5-Pad-)") (class "Default")
      (node (ref "C5") (pin "-") (pinfunction "-_-") (pintype "passive"))
    )
    (net (code "105") (name "unconnected-(IC2-~{INT}-Pad13)") (class "Default")
      (node (ref "IC2") (pin "13") (pinfunction "~{INT}_13") (pintype "output"))
    )
    (net (code "106") (name "unconnected-(IC4-I5-Pad5)") (class "Default")
      (node (ref "IC4") (pin "5") (pinfunction "I5_5") (pintype "input"))
    )
    (net (code "107") (name "unconnected-(IC4-I6-Pad6)") (class "Default")
      (node (ref "IC4") (pin "6") (pinfunction "I6_6") (pintype "input"))
    )
    (net (code "108") (name "unconnected-(IC4-I7-Pad7)") (class "Default")
      (node (ref "IC4") (pin "7") (pinfunction "I7_7") (pintype "input"))
    )
    (net (code "109") (name "unconnected-(IC4-O5-Pad12)") (class "Default")
      (node (ref "IC4") (pin "12") (pinfunction "O5_12") (pintype "open_collector"))
    )
    (net (code "110") (name "unconnected-(IC4-O6-Pad11)") (class "Default")
      (node (ref "IC4") (pin "11") (pinfunction "O6_11") (pintype "open_collector"))
    )
    (net (code "111") (name "unconnected-(IC4-O7-Pad10)") (class "Default")
      (node (ref "IC4") (pin "10") (pinfunction "O7_10") (pintype "open_collector"))
    )
    (net (code "112") (name "unconnected-(IC5-~{INT}-Pad13)") (class "Default")
      (node (ref "IC5") (pin "13") (pinfunction "~{INT}_13") (pintype "output"))
    )
    (net (code "113") (name "unconnected-(IC8-VO-Pad3)") (class "Default")
      (node (ref "IC8") (pin "3") (pinfunction "VO_3") (pintype "passive"))
    )
    (net (code "114") (name "unconnected-(J4-Pad1)") (class "Default")
      (node (ref "J4") (pin "1") (pinfunction "1_1") (pintype "passive"))
    )
    (net (code "115") (name "unconnected-(J4-Pad2)") (class "Default")
      (node (ref "J4") (pin "2") (pinfunction "2_2") (pintype "passive"))
    )
    (net (code "116") (name "unconnected-(J4-Pad3)") (class "Default")
      (node (ref "J4") (pin "3") (pinfunction "3_3") (pintype "passive"))
    )
    (net (code "117") (name "unconnected-(J4-Pad4)") (class "Default")
      (node (ref "J4") (pin "4") (pinfunction "4_4") (pintype "passive"))
    )
  )
)
